# Isolated_Interface.net
KiCad netlist of a schematic drawn in Altium Designer
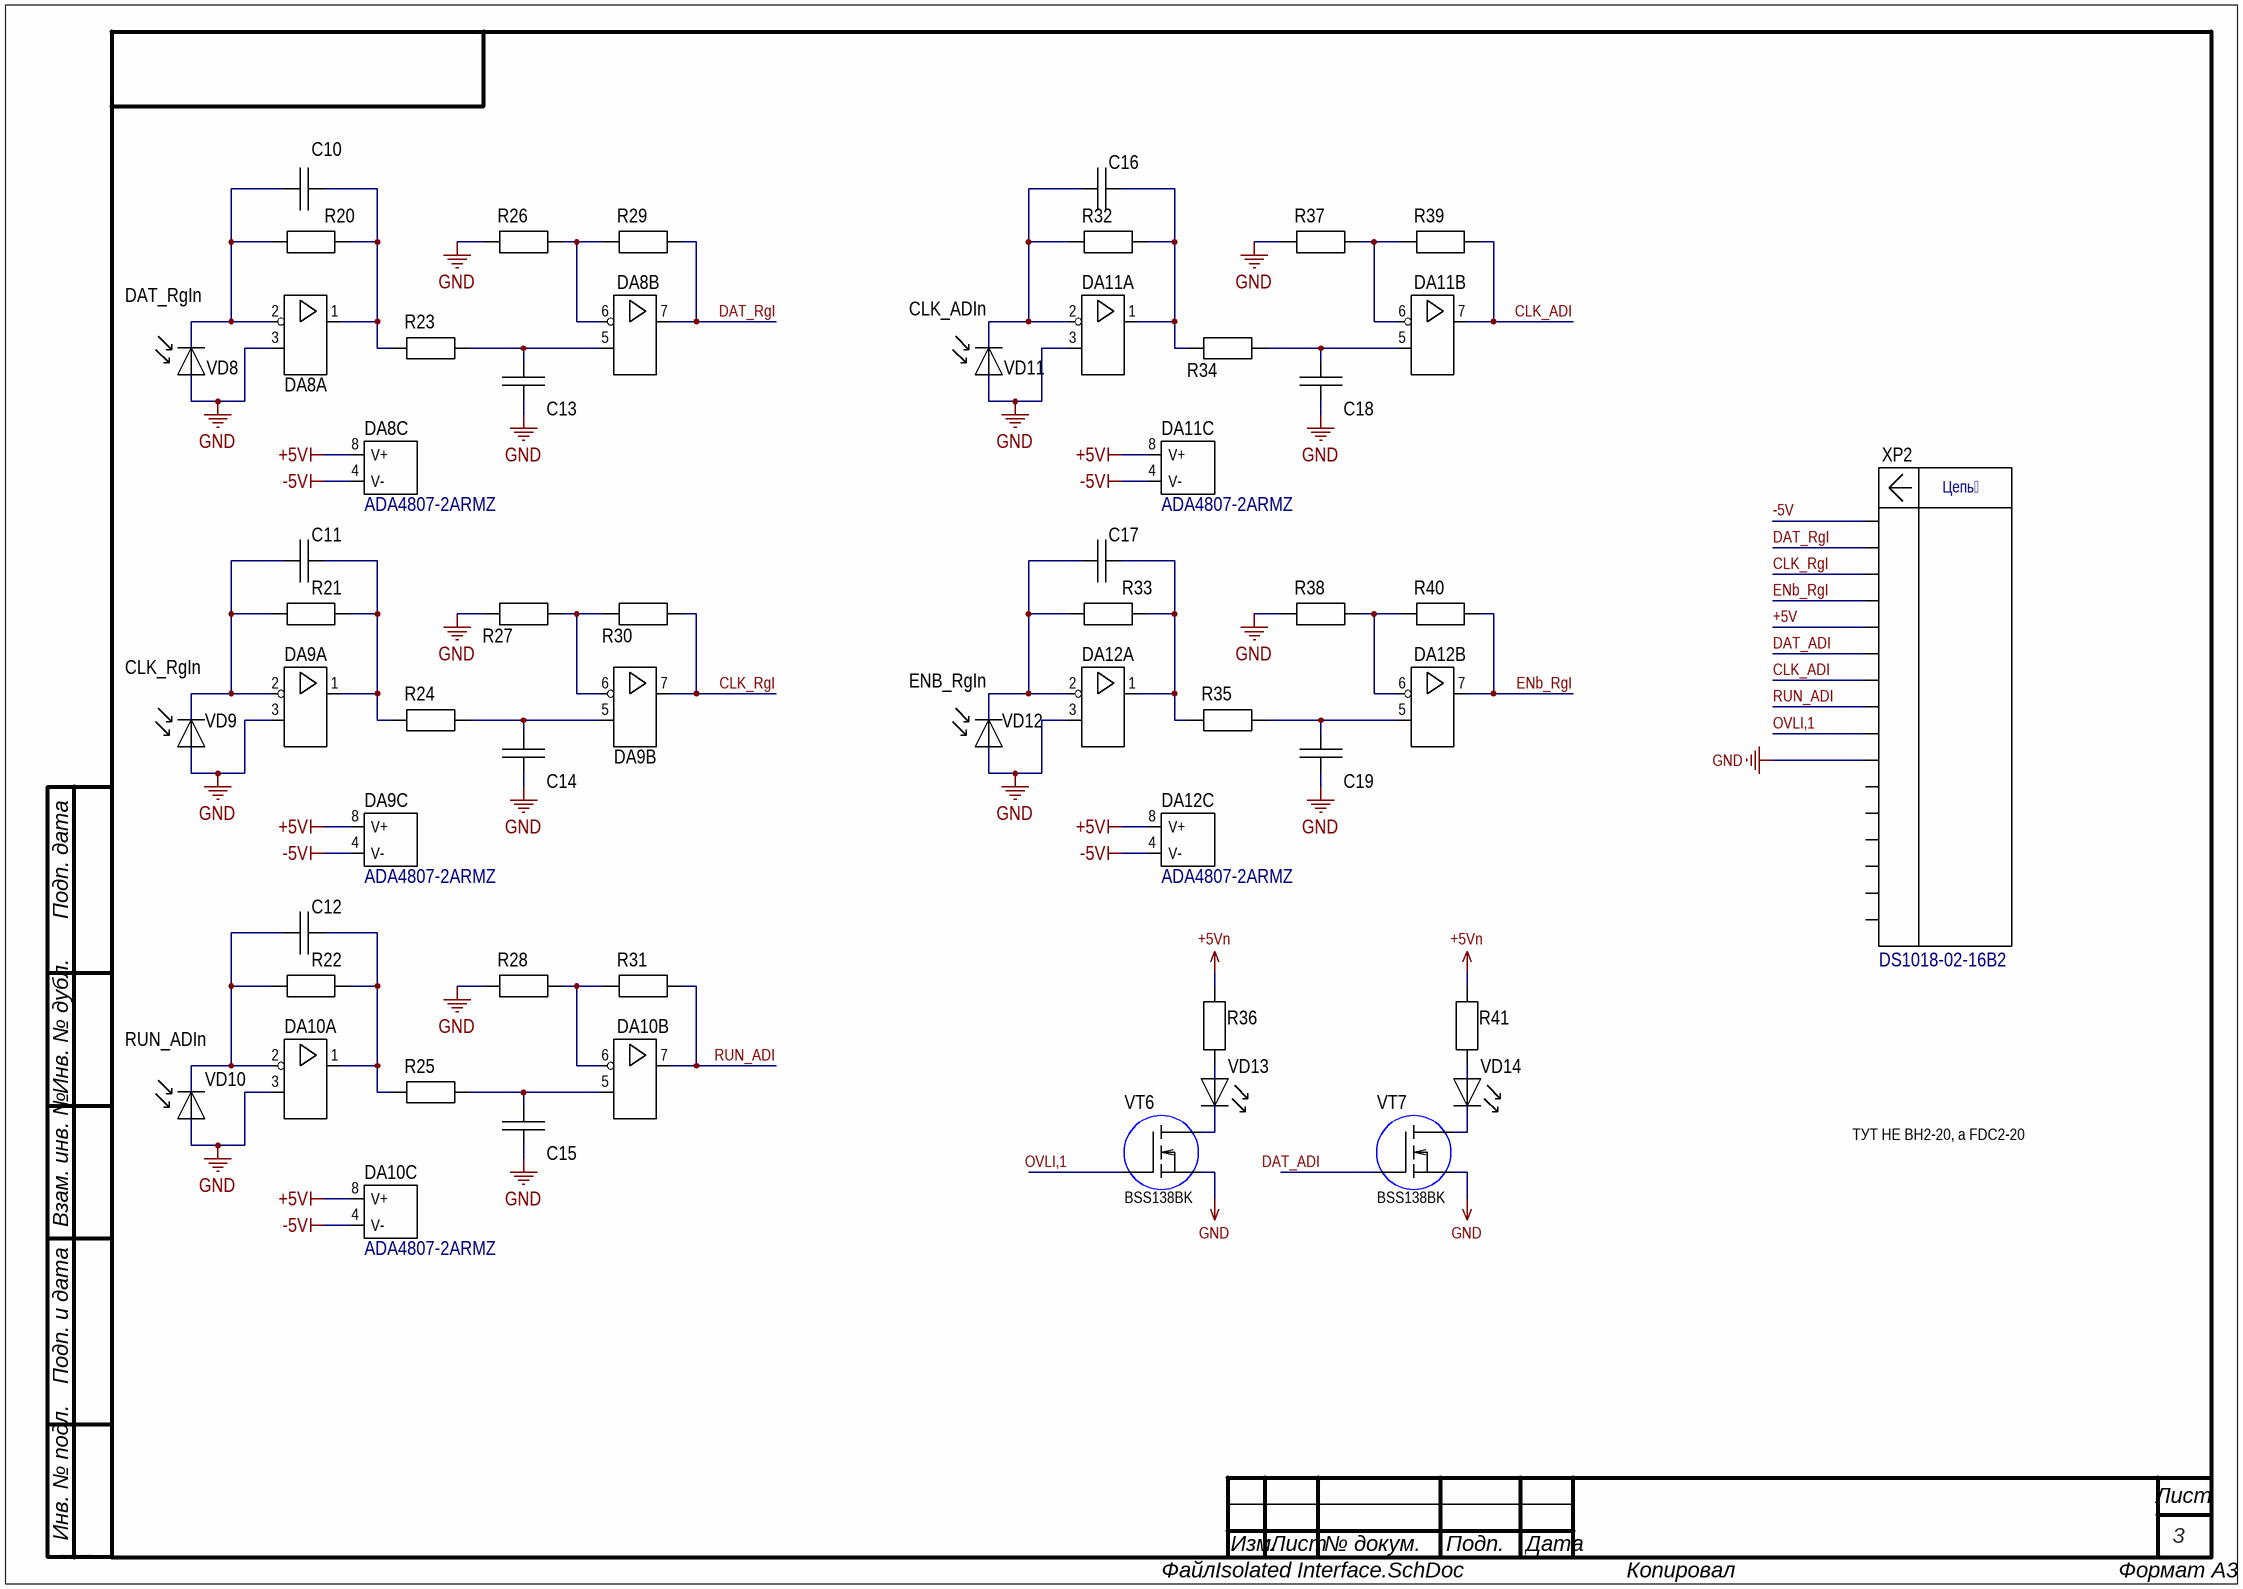
[diagram p0: Isolated Interface.SchDoc]

(export (version "E")
  (design (tool "Eeschema 10.0.6"))
  (components
    (comp (ref "C10")
      (value "0805-NP0-50 В-2,4 пФ-1%")
      (footprint "standard-case:CAP: 0805")
      (libsource (lib "МНИПИ_Конденсаторы") (part "0805-NP0-50 В-2,4 пФ-1%"))
    )
    (comp (ref "C11")
      (value "0805-NP0-50 В-2,4 пФ-1%")
      (footprint "standard-case:CAP: 0805")
      (libsource (lib "МНИПИ_Конденсаторы") (part "0805-NP0-50 В-2,4 пФ-1%"))
    )
    (comp (ref "C12")
      (value "0805-NP0-50 В-2,4 пФ-1%")
      (footprint "standard-case:CAP: 0805")
      (libsource (lib "МНИПИ_Конденсаторы") (part "0805-NP0-50 В-2,4 пФ-1%"))
    )
    (comp (ref "C13")
      (value "1206-С0G-50 B-56 пФ+-1%")
      (footprint "standard-case:CAP: 1206")
      (libsource (lib "МНИПИ_Конденсаторы") (part "1206-С0G-50 B-56 пФ+-1%"))
    )
    (comp (ref "C14")
      (value "1206-С0G-50 B-56 пФ+-1%")
      (footprint "standard-case:CAP: 1206")
      (libsource (lib "МНИПИ_Конденсаторы") (part "1206-С0G-50 B-56 пФ+-1%"))
    )
    (comp (ref "C15")
      (value "1206-С0G-50 B-56 пФ+-1%")
      (footprint "standard-case:CAP: 1206")
      (libsource (lib "МНИПИ_Конденсаторы") (part "1206-С0G-50 B-56 пФ+-1%"))
    )
    (comp (ref "C16")
      (value "0805-NP0-50 В-2,4 пФ-1%")
      (footprint "standard-case:CAP: 0805")
      (libsource (lib "МНИПИ_Конденсаторы") (part "0805-NP0-50 В-2,4 пФ-1%"))
    )
    (comp (ref "C17")
      (value "0805-NP0-50 В-2,4 пФ-1%")
      (footprint "standard-case:CAP: 0805")
      (libsource (lib "МНИПИ_Конденсаторы") (part "0805-NP0-50 В-2,4 пФ-1%"))
    )
    (comp (ref "C18")
      (value "1206-С0G-50 B-56 пФ+-1%")
      (footprint "standard-case:CAP: 1206")
      (libsource (lib "МНИПИ_Конденсаторы") (part "1206-С0G-50 B-56 пФ+-1%"))
    )
    (comp (ref "C19")
      (value "1206-С0G-50 B-56 пФ+-1%")
      (footprint "standard-case:CAP: 1206")
      (libsource (lib "МНИПИ_Конденсаторы") (part "1206-С0G-50 B-56 пФ+-1%"))
    )
    (comp (ref "DA8")
      (value "ADA4807-2ARMZ")
      (footprint "8-MSOP")
      (description "3.1 nV/√Hz, 1 mA, 180 MHz,\r\nRail-to-Rail Input/Output Amplifiers")
      (libsource (lib "МНИПИ_Микросхемы") (part "ADA4807-2ARMZ"))
    )
    (comp (ref "DA9")
      (value "ADA4807-2ARMZ")
      (footprint "8-MSOP")
      (description "3.1 nV/√Hz, 1 mA, 180 MHz,\r\nRail-to-Rail Input/Output Amplifiers")
      (libsource (lib "МНИПИ_Микросхемы") (part "ADA4807-2ARMZ"))
    )
    (comp (ref "DA10")
      (value "ADA4807-2ARMZ")
      (footprint "8-MSOP")
      (description "3.1 nV/√Hz, 1 mA, 180 MHz,\r\nRail-to-Rail Input/Output Amplifiers")
      (libsource (lib "МНИПИ_Микросхемы") (part "ADA4807-2ARMZ"))
    )
    (comp (ref "DA11")
      (value "ADA4807-2ARMZ")
      (footprint "8-MSOP")
      (description "3.1 nV/√Hz, 1 mA, 180 MHz,\r\nRail-to-Rail Input/Output Amplifiers")
      (libsource (lib "МНИПИ_Микросхемы") (part "ADA4807-2ARMZ"))
    )
    (comp (ref "DA12")
      (value "ADA4807-2ARMZ")
      (footprint "8-MSOP")
      (description "3.1 nV/√Hz, 1 mA, 180 MHz,\r\nRail-to-Rail Input/Output Amplifiers")
      (libsource (lib "МНИПИ_Микросхемы") (part "ADA4807-2ARMZ"))
    )
    (comp (ref "R20")
      (value "1206-5,23 кОм+-1%")
      (footprint "МНИПИ_Резисторы:1206")
      (libsource (lib "МНИПИ_Резисторы") (part "1206-5,23 кОм+-1%"))
    )
    (comp (ref "R21")
      (value "1206-5,23 кОм+-1%")
      (footprint "МНИПИ_Резисторы:1206")
      (libsource (lib "МНИПИ_Резисторы") (part "1206-5,23 кОм+-1%"))
    )
    (comp (ref "R22")
      (value "1206-5,23 кОм+-1%")
      (footprint "МНИПИ_Резисторы:1206")
      (libsource (lib "МНИПИ_Резисторы") (part "1206-5,23 кОм+-1%"))
    )
    (comp (ref "R23")
      (value "1206-140 Ом+-1%")
      (footprint "МНИПИ_Резисторы:1206")
      (libsource (lib "МНИПИ_Резисторы") (part "1206-140 Ом+-1%"))
    )
    (comp (ref "R24")
      (value "1206-140 Ом+-1%")
      (footprint "МНИПИ_Резисторы:1206")
      (libsource (lib "МНИПИ_Резисторы") (part "1206-140 Ом+-1%"))
    )
    (comp (ref "R25")
      (value "1206-140 Ом+-1%")
      (footprint "МНИПИ_Резисторы:1206")
      (libsource (lib "МНИПИ_Резисторы") (part "1206-140 Ом+-1%"))
    )
    (comp (ref "R26")
      (value "1206-102 Ом+-1%")
      (footprint "МНИПИ_Резисторы:1206")
      (libsource (lib "МНИПИ_Резисторы") (part "1206-102 Ом+-1%"))
    )
    (comp (ref "R27")
      (value "1206-102 Ом+-1%")
      (footprint "МНИПИ_Резисторы:1206")
      (libsource (lib "МНИПИ_Резисторы") (part "1206-102 Ом+-1%"))
    )
    (comp (ref "R28")
      (value "1206-102 Ом+-1%")
      (footprint "МНИПИ_Резисторы:1206")
      (libsource (lib "МНИПИ_Резисторы") (part "1206-102 Ом+-1%"))
    )
    (comp (ref "R29")
      (value "1206-215 Ом+-1%")
      (footprint "МНИПИ_Резисторы:1206")
      (libsource (lib "МНИПИ_Резисторы") (part "1206-215 Ом+-1%"))
    )
    (comp (ref "R30")
      (value "1206-215 Ом+-1%")
      (footprint "МНИПИ_Резисторы:1206")
      (libsource (lib "МНИПИ_Резисторы") (part "1206-215 Ом+-1%"))
    )
    (comp (ref "R31")
      (value "1206-215 Ом+-1%")
      (footprint "МНИПИ_Резисторы:1206")
      (libsource (lib "МНИПИ_Резисторы") (part "1206-215 Ом+-1%"))
    )
    (comp (ref "R32")
      (value "1206-5,23 кОм+-1%")
      (footprint "МНИПИ_Резисторы:1206")
      (libsource (lib "МНИПИ_Резисторы") (part "1206-5,23 кОм+-1%"))
    )
    (comp (ref "R33")
      (value "1206-5,23 кОм+-1%")
      (footprint "МНИПИ_Резисторы:1206")
      (libsource (lib "МНИПИ_Резисторы") (part "1206-5,23 кОм+-1%"))
    )
    (comp (ref "R34")
      (value "1206-140 Ом+-1%")
      (footprint "МНИПИ_Резисторы:1206")
      (libsource (lib "МНИПИ_Резисторы") (part "1206-140 Ом+-1%"))
    )
    (comp (ref "R35")
      (value "1206-140 Ом+-1%")
      (footprint "МНИПИ_Резисторы:1206")
      (libsource (lib "МНИПИ_Резисторы") (part "1206-140 Ом+-1%"))
    )
    (comp (ref "R36")
      (value "1206-30 Ом+-5%")
      (footprint "МНИПИ_Резисторы:1206")
      (libsource (lib "МНИПИ_Резисторы") (part "1206-30 Ом+-5%"))
    )
    (comp (ref "R37")
      (value "1206-102 Ом+-1%")
      (footprint "МНИПИ_Резисторы:1206")
      (libsource (lib "МНИПИ_Резисторы") (part "1206-102 Ом+-1%"))
    )
    (comp (ref "R38")
      (value "1206-102 Ом+-1%")
      (footprint "МНИПИ_Резисторы:1206")
      (libsource (lib "МНИПИ_Резисторы") (part "1206-102 Ом+-1%"))
    )
    (comp (ref "R39")
      (value "1206-215 Ом+-1%")
      (footprint "МНИПИ_Резисторы:1206")
      (libsource (lib "МНИПИ_Резисторы") (part "1206-215 Ом+-1%"))
    )
    (comp (ref "R40")
      (value "1206-215 Ом+-1%")
      (footprint "МНИПИ_Резисторы:1206")
      (libsource (lib "МНИПИ_Резисторы") (part "1206-215 Ом+-1%"))
    )
    (comp (ref "R41")
      (value "1206-30 Ом+-5%")
      (footprint "МНИПИ_Резисторы:1206")
      (libsource (lib "МНИПИ_Резисторы") (part "1206-30 Ом+-5%"))
    )
    (comp (ref "VD8")
      (value "SFH203")
      (footprint "SFH203")
      (description "Silicon PIN Photodiode")
      (libsource (lib "МНИПИ_Диоды") (part "SFH203"))
    )
    (comp (ref "VD9")
      (value "SFH203")
      (footprint "SFH203")
      (description "Silicon PIN Photodiode")
      (libsource (lib "МНИПИ_Диоды") (part "SFH203"))
    )
    (comp (ref "VD10")
      (value "SFH203")
      (footprint "SFH203")
      (description "Silicon PIN Photodiode")
      (libsource (lib "МНИПИ_Диоды") (part "SFH203"))
    )
    (comp (ref "VD11")
      (value "SFH203")
      (footprint "SFH203")
      (description "Silicon PIN Photodiode")
      (libsource (lib "МНИПИ_Диоды") (part "SFH203"))
    )
    (comp (ref "VD12")
      (value "SFH203")
      (footprint "SFH203")
      (description "Silicon PIN Photodiode")
      (libsource (lib "МНИПИ_Диоды") (part "SFH203"))
    )
    (comp (ref "VD13")
      (value "VSMY2853RG")
      (footprint "VSMY2853G")
      (description "High Speed Infrared Emitting Diodes, 850 nm,\r\nSurface Emitter Technology")
      (libsource (lib "МНИПИ_Диоды") (part "VSMY2853RG"))
    )
    (comp (ref "VD14")
      (value "VSMY2853RG")
      (footprint "VSMY2853G")
      (description "High Speed Infrared Emitting Diodes, 850 nm,\r\nSurface Emitter Technology")
      (libsource (lib "МНИПИ_Диоды") (part "VSMY2853RG"))
    )
    (comp (ref "VT6")
      (value "BSS138BK")
      (footprint "SOT-23-3")
      (description "60 V, 360 mA N-channel Trench MOSFET")
      (libsource (lib "МНИПИ_Транзисторы") (part "BSS138BK"))
    )
    (comp (ref "VT7")
      (value "BSS138BK")
      (footprint "SOT-23-3")
      (description "60 V, 360 mA N-channel Trench MOSFET")
      (libsource (lib "МНИПИ_Транзисторы") (part "BSS138BK"))
    )
    (comp (ref "XP2")
      (value "DS1018-02-16B2")
      (footprint "DS1018-02-16B2")
      (description "pitch 2mm, 20 pin 2x10")
      (libsource (lib "МНИПИ_Разъемы") (part "DS1018-02-16B2"))
    )
  )
  (nets
    (net (code "1") (name "+5V") (class "Default")
      (node (ref "DA10") (pin "8") (pinfunction "V+_8") (pintype "passive"))
      (node (ref "DA11") (pin "8") (pinfunction "V+_8") (pintype "passive"))
      (node (ref "DA12") (pin "8") (pinfunction "V+_8") (pintype "passive"))
      (node (ref "DA8") (pin "8") (pinfunction "V+_8") (pintype "passive"))
      (node (ref "DA9") (pin "8") (pinfunction "V+_8") (pintype "passive"))
      (node (ref "XP2") (pin "5") (pinfunction "5_5") (pintype "passive"))
    )
    (net (code "2") (name "+5Vn") (class "Default")
      (node (ref "R36") (pin "2") (pinfunction "2_2") (pintype "passive"))
      (node (ref "R41") (pin "2") (pinfunction "2_2") (pintype "passive"))
    )
    (net (code "3") (name "-5V") (class "Default")
      (node (ref "DA10") (pin "4") (pinfunction "V-_4") (pintype "passive"))
      (node (ref "DA11") (pin "4") (pinfunction "V-_4") (pintype "passive"))
      (node (ref "DA12") (pin "4") (pinfunction "V-_4") (pintype "passive"))
      (node (ref "DA8") (pin "4") (pinfunction "V-_4") (pintype "passive"))
      (node (ref "DA9") (pin "4") (pinfunction "V-_4") (pintype "passive"))
      (node (ref "XP2") (pin "1") (pinfunction "1_1") (pintype "passive"))
    )
    (net (code "4") (name "/CLK_ADI") (class "Default")
      (node (ref "DA11") (pin "7") (pinfunction "OUT_B_7") (pintype "passive"))
      (node (ref "R39") (pin "2") (pinfunction "2_2") (pintype "passive"))
      (node (ref "XP2") (pin "7") (pinfunction "7_7") (pintype "passive"))
    )
    (net (code "5") (name "/CLK_RgI") (class "Default")
      (node (ref "DA9") (pin "7") (pinfunction "OUT_B_7") (pintype "passive"))
      (node (ref "R30") (pin "2") (pinfunction "2_2") (pintype "passive"))
      (node (ref "XP2") (pin "3") (pinfunction "3_3") (pintype "passive"))
    )
    (net (code "6") (name "/DAT_ADI") (class "Default")
      (node (ref "VT7") (pin "1") (pinfunction "G_1") (pintype "passive"))
      (node (ref "XP2") (pin "6") (pinfunction "6_6") (pintype "passive"))
    )
    (net (code "7") (name "/DAT_RgI") (class "Default")
      (node (ref "DA8") (pin "7") (pinfunction "OUT_B_7") (pintype "passive"))
      (node (ref "R29") (pin "2") (pinfunction "2_2") (pintype "passive"))
      (node (ref "XP2") (pin "2") (pinfunction "2_2") (pintype "passive"))
    )
    (net (code "8") (name "/ENb_RgI") (class "Default")
      (node (ref "DA12") (pin "7") (pinfunction "OUT_B_7") (pintype "passive"))
      (node (ref "R40") (pin "2") (pinfunction "2_2") (pintype "passive"))
      (node (ref "XP2") (pin "4") (pinfunction "4_4") (pintype "passive"))
    )
    (net (code "9") (name "/OVLI,1") (class "Default")
      (node (ref "VT6") (pin "1") (pinfunction "G_1") (pintype "passive"))
      (node (ref "XP2") (pin "9") (pinfunction "9_9") (pintype "passive"))
    )
    (net (code "10") (name "/RUN_ADI") (class "Default")
      (node (ref "DA10") (pin "7") (pinfunction "OUT_B_7") (pintype "passive"))
      (node (ref "R31") (pin "2") (pinfunction "2_2") (pintype "passive"))
      (node (ref "XP2") (pin "8") (pinfunction "8_8") (pintype "passive"))
    )
    (net (code "11") (name "GND") (class "Default")
      (node (ref "C13") (pin "1") (pinfunction "1_1") (pintype "passive"))
      (node (ref "C14") (pin "1") (pinfunction "1_1") (pintype "passive"))
      (node (ref "C15") (pin "1") (pinfunction "1_1") (pintype "passive"))
      (node (ref "C18") (pin "1") (pinfunction "1_1") (pintype "passive"))
      (node (ref "C19") (pin "1") (pinfunction "1_1") (pintype "passive"))
      (node (ref "DA10") (pin "3") (pinfunction "+IN_A_3") (pintype "passive"))
      (node (ref "DA11") (pin "3") (pinfunction "+IN_A_3") (pintype "passive"))
      (node (ref "DA12") (pin "3") (pinfunction "+IN_A_3") (pintype "passive"))
      (node (ref "DA8") (pin "3") (pinfunction "+IN_A_3") (pintype "passive"))
      (node (ref "DA9") (pin "3") (pinfunction "+IN_A_3") (pintype "passive"))
      (node (ref "R26") (pin "1") (pinfunction "1_1") (pintype "passive"))
      (node (ref "R27") (pin "1") (pinfunction "1_1") (pintype "passive"))
      (node (ref "R28") (pin "1") (pinfunction "1_1") (pintype "passive"))
      (node (ref "R37") (pin "1") (pinfunction "1_1") (pintype "passive"))
      (node (ref "R38") (pin "1") (pinfunction "1_1") (pintype "passive"))
      (node (ref "VD10") (pin "1") (pintype "passive"))
      (node (ref "VD11") (pin "1") (pintype "passive"))
      (node (ref "VD12") (pin "1") (pintype "passive"))
      (node (ref "VD8") (pin "1") (pintype "passive"))
      (node (ref "VD9") (pin "1") (pintype "passive"))
      (node (ref "VT6") (pin "2") (pinfunction "S_2") (pintype "passive"))
      (node (ref "VT7") (pin "2") (pinfunction "S_2") (pintype "passive"))
      (node (ref "XP2") (pin "10") (pinfunction "10_10") (pintype "passive"))
    )
    (net (code "12") (name "Net-(DA8A--IN_A)") (class "Default")
      (node (ref "C10") (pin "1") (pinfunction "1_1") (pintype "passive"))
      (node (ref "DA8") (pin "2") (pinfunction "-IN_A_2") (pintype "passive"))
      (node (ref "R20") (pin "1") (pinfunction "1_1") (pintype "passive"))
      (node (ref "VD8") (pin "2") (pintype "passive"))
    )
    (net (code "13") (name "Net-(DA8A-OUT_A)") (class "Default")
      (node (ref "C10") (pin "2") (pinfunction "2_2") (pintype "passive"))
      (node (ref "DA8") (pin "1") (pinfunction "OUT_A_1") (pintype "passive"))
      (node (ref "R20") (pin "2") (pinfunction "2_2") (pintype "passive"))
      (node (ref "R23") (pin "1") (pinfunction "1_1") (pintype "passive"))
    )
    (net (code "14") (name "Net-(DA8B-+IN_B)") (class "Default")
      (node (ref "C13") (pin "2") (pinfunction "2_2") (pintype "passive"))
      (node (ref "DA8") (pin "5") (pinfunction "+IN_B_5") (pintype "passive"))
      (node (ref "R23") (pin "2") (pinfunction "2_2") (pintype "passive"))
    )
    (net (code "15") (name "Net-(DA8B--IN_B)") (class "Default")
      (node (ref "DA8") (pin "6") (pinfunction "-IN_B_6") (pintype "passive"))
      (node (ref "R26") (pin "2") (pinfunction "2_2") (pintype "passive"))
      (node (ref "R29") (pin "1") (pinfunction "1_1") (pintype "passive"))
    )
    (net (code "16") (name "Net-(DA9A--IN_A)") (class "Default")
      (node (ref "C11") (pin "1") (pinfunction "1_1") (pintype "passive"))
      (node (ref "DA9") (pin "2") (pinfunction "-IN_A_2") (pintype "passive"))
      (node (ref "R21") (pin "1") (pinfunction "1_1") (pintype "passive"))
      (node (ref "VD9") (pin "2") (pintype "passive"))
    )
    (net (code "17") (name "Net-(DA9A-OUT_A)") (class "Default")
      (node (ref "C11") (pin "2") (pinfunction "2_2") (pintype "passive"))
      (node (ref "DA9") (pin "1") (pinfunction "OUT_A_1") (pintype "passive"))
      (node (ref "R21") (pin "2") (pinfunction "2_2") (pintype "passive"))
      (node (ref "R24") (pin "1") (pinfunction "1_1") (pintype "passive"))
    )
    (net (code "18") (name "Net-(DA9B-+IN_B)") (class "Default")
      (node (ref "C14") (pin "2") (pinfunction "2_2") (pintype "passive"))
      (node (ref "DA9") (pin "5") (pinfunction "+IN_B_5") (pintype "passive"))
      (node (ref "R24") (pin "2") (pinfunction "2_2") (pintype "passive"))
    )
    (net (code "19") (name "Net-(DA9B--IN_B)") (class "Default")
      (node (ref "DA9") (pin "6") (pinfunction "-IN_B_6") (pintype "passive"))
      (node (ref "R27") (pin "2") (pinfunction "2_2") (pintype "passive"))
      (node (ref "R30") (pin "1") (pinfunction "1_1") (pintype "passive"))
    )
    (net (code "20") (name "Net-(DA10A--IN_A)") (class "Default")
      (node (ref "C12") (pin "1") (pinfunction "1_1") (pintype "passive"))
      (node (ref "DA10") (pin "2") (pinfunction "-IN_A_2") (pintype "passive"))
      (node (ref "R22") (pin "1") (pinfunction "1_1") (pintype "passive"))
      (node (ref "VD10") (pin "2") (pintype "passive"))
    )
    (net (code "21") (name "Net-(DA10A-OUT_A)") (class "Default")
      (node (ref "C12") (pin "2") (pinfunction "2_2") (pintype "passive"))
      (node (ref "DA10") (pin "1") (pinfunction "OUT_A_1") (pintype "passive"))
      (node (ref "R22") (pin "2") (pinfunction "2_2") (pintype "passive"))
      (node (ref "R25") (pin "1") (pinfunction "1_1") (pintype "passive"))
    )
    (net (code "22") (name "Net-(DA10B-+IN_B)") (class "Default")
      (node (ref "C15") (pin "2") (pinfunction "2_2") (pintype "passive"))
      (node (ref "DA10") (pin "5") (pinfunction "+IN_B_5") (pintype "passive"))
      (node (ref "R25") (pin "2") (pinfunction "2_2") (pintype "passive"))
    )
    (net (code "23") (name "Net-(DA10B--IN_B)") (class "Default")
      (node (ref "DA10") (pin "6") (pinfunction "-IN_B_6") (pintype "passive"))
      (node (ref "R28") (pin "2") (pinfunction "2_2") (pintype "passive"))
      (node (ref "R31") (pin "1") (pinfunction "1_1") (pintype "passive"))
    )
    (net (code "24") (name "Net-(DA11A--IN_A)") (class "Default")
      (node (ref "C16") (pin "1") (pinfunction "1_1") (pintype "passive"))
      (node (ref "DA11") (pin "2") (pinfunction "-IN_A_2") (pintype "passive"))
      (node (ref "R32") (pin "1") (pinfunction "1_1") (pintype "passive"))
      (node (ref "VD11") (pin "2") (pintype "passive"))
    )
    (net (code "25") (name "Net-(DA11A-OUT_A)") (class "Default")
      (node (ref "C16") (pin "2") (pinfunction "2_2") (pintype "passive"))
      (node (ref "DA11") (pin "1") (pinfunction "OUT_A_1") (pintype "passive"))
      (node (ref "R32") (pin "2") (pinfunction "2_2") (pintype "passive"))
      (node (ref "R34") (pin "1") (pinfunction "1_1") (pintype "passive"))
    )
    (net (code "26") (name "Net-(DA11B-+IN_B)") (class "Default")
      (node (ref "C18") (pin "2") (pinfunction "2_2") (pintype "passive"))
      (node (ref "DA11") (pin "5") (pinfunction "+IN_B_5") (pintype "passive"))
      (node (ref "R34") (pin "2") (pinfunction "2_2") (pintype "passive"))
    )
    (net (code "27") (name "Net-(DA11B--IN_B)") (class "Default")
      (node (ref "DA11") (pin "6") (pinfunction "-IN_B_6") (pintype "passive"))
      (node (ref "R37") (pin "2") (pinfunction "2_2") (pintype "passive"))
      (node (ref "R39") (pin "1") (pinfunction "1_1") (pintype "passive"))
    )
    (net (code "28") (name "Net-(DA12A--IN_A)") (class "Default")
      (node (ref "C17") (pin "1") (pinfunction "1_1") (pintype "passive"))
      (node (ref "DA12") (pin "2") (pinfunction "-IN_A_2") (pintype "passive"))
      (node (ref "R33") (pin "1") (pinfunction "1_1") (pintype "passive"))
      (node (ref "VD12") (pin "2") (pintype "passive"))
    )
    (net (code "29") (name "Net-(DA12A-OUT_A)") (class "Default")
      (node (ref "C17") (pin "2") (pinfunction "2_2") (pintype "passive"))
      (node (ref "DA12") (pin "1") (pinfunction "OUT_A_1") (pintype "passive"))
      (node (ref "R33") (pin "2") (pinfunction "2_2") (pintype "passive"))
      (node (ref "R35") (pin "1") (pinfunction "1_1") (pintype "passive"))
    )
    (net (code "30") (name "Net-(DA12B-+IN_B)") (class "Default")
      (node (ref "C19") (pin "2") (pinfunction "2_2") (pintype "passive"))
      (node (ref "DA12") (pin "5") (pinfunction "+IN_B_5") (pintype "passive"))
      (node (ref "R35") (pin "2") (pinfunction "2_2") (pintype "passive"))
    )
    (net (code "31") (name "Net-(DA12B--IN_B)") (class "Default")
      (node (ref "DA12") (pin "6") (pinfunction "-IN_B_6") (pintype "passive"))
      (node (ref "R38") (pin "2") (pinfunction "2_2") (pintype "passive"))
      (node (ref "R40") (pin "1") (pinfunction "1_1") (pintype "passive"))
    )
    (net (code "32") (name "Net-(VD13-Anode)") (class "Default")
      (node (ref "R36") (pin "1") (pinfunction "1_1") (pintype "passive"))
      (node (ref "VD13") (pin "1") (pinfunction "Anode_1") (pintype "passive"))
    )
    (net (code "33") (name "Net-(VD13-Cathode)") (class "Default")
      (node (ref "VD13") (pin "2") (pinfunction "Cathode_2") (pintype "passive"))
      (node (ref "VT6") (pin "3") (pinfunction "D_3") (pintype "passive"))
    )
    (net (code "34") (name "Net-(VD14-Anode)") (class "Default")
      (node (ref "R41") (pin "1") (pinfunction "1_1") (pintype "passive"))
      (node (ref "VD14") (pin "1") (pinfunction "Anode_1") (pintype "passive"))
    )
    (net (code "35") (name "Net-(VD14-Cathode)") (class "Default")
      (node (ref "VD14") (pin "2") (pinfunction "Cathode_2") (pintype "passive"))
      (node (ref "VT7") (pin "3") (pinfunction "D_3") (pintype "passive"))
    )
    (net (code "36") (name "unconnected-(XP2-Pad11)") (class "Default")
      (node (ref "XP2") (pin "11") (pinfunction "11_11") (pintype "passive"))
    )
    (net (code "37") (name "unconnected-(XP2-Pad12)") (class "Default")
      (node (ref "XP2") (pin "12") (pinfunction "12_12") (pintype "passive"))
    )
    (net (code "38") (name "unconnected-(XP2-Pad13)") (class "Default")
      (node (ref "XP2") (pin "13") (pinfunction "13_13") (pintype "passive"))
    )
    (net (code "39") (name "unconnected-(XP2-Pad14)") (class "Default")
      (node (ref "XP2") (pin "14") (pinfunction "14_14") (pintype "passive"))
    )
    (net (code "40") (name "unconnected-(XP2-Pad15)") (class "Default")
      (node (ref "XP2") (pin "15") (pinfunction "15_15") (pintype "passive"))
    )
    (net (code "41") (name "unconnected-(XP2-Pad16)") (class "Default")
      (node (ref "XP2") (pin "16") (pinfunction "16_16") (pintype "passive"))
    )
  )
)
